# HeaderA.net
KiCad netlist of a schematic drawn in Altium Designer
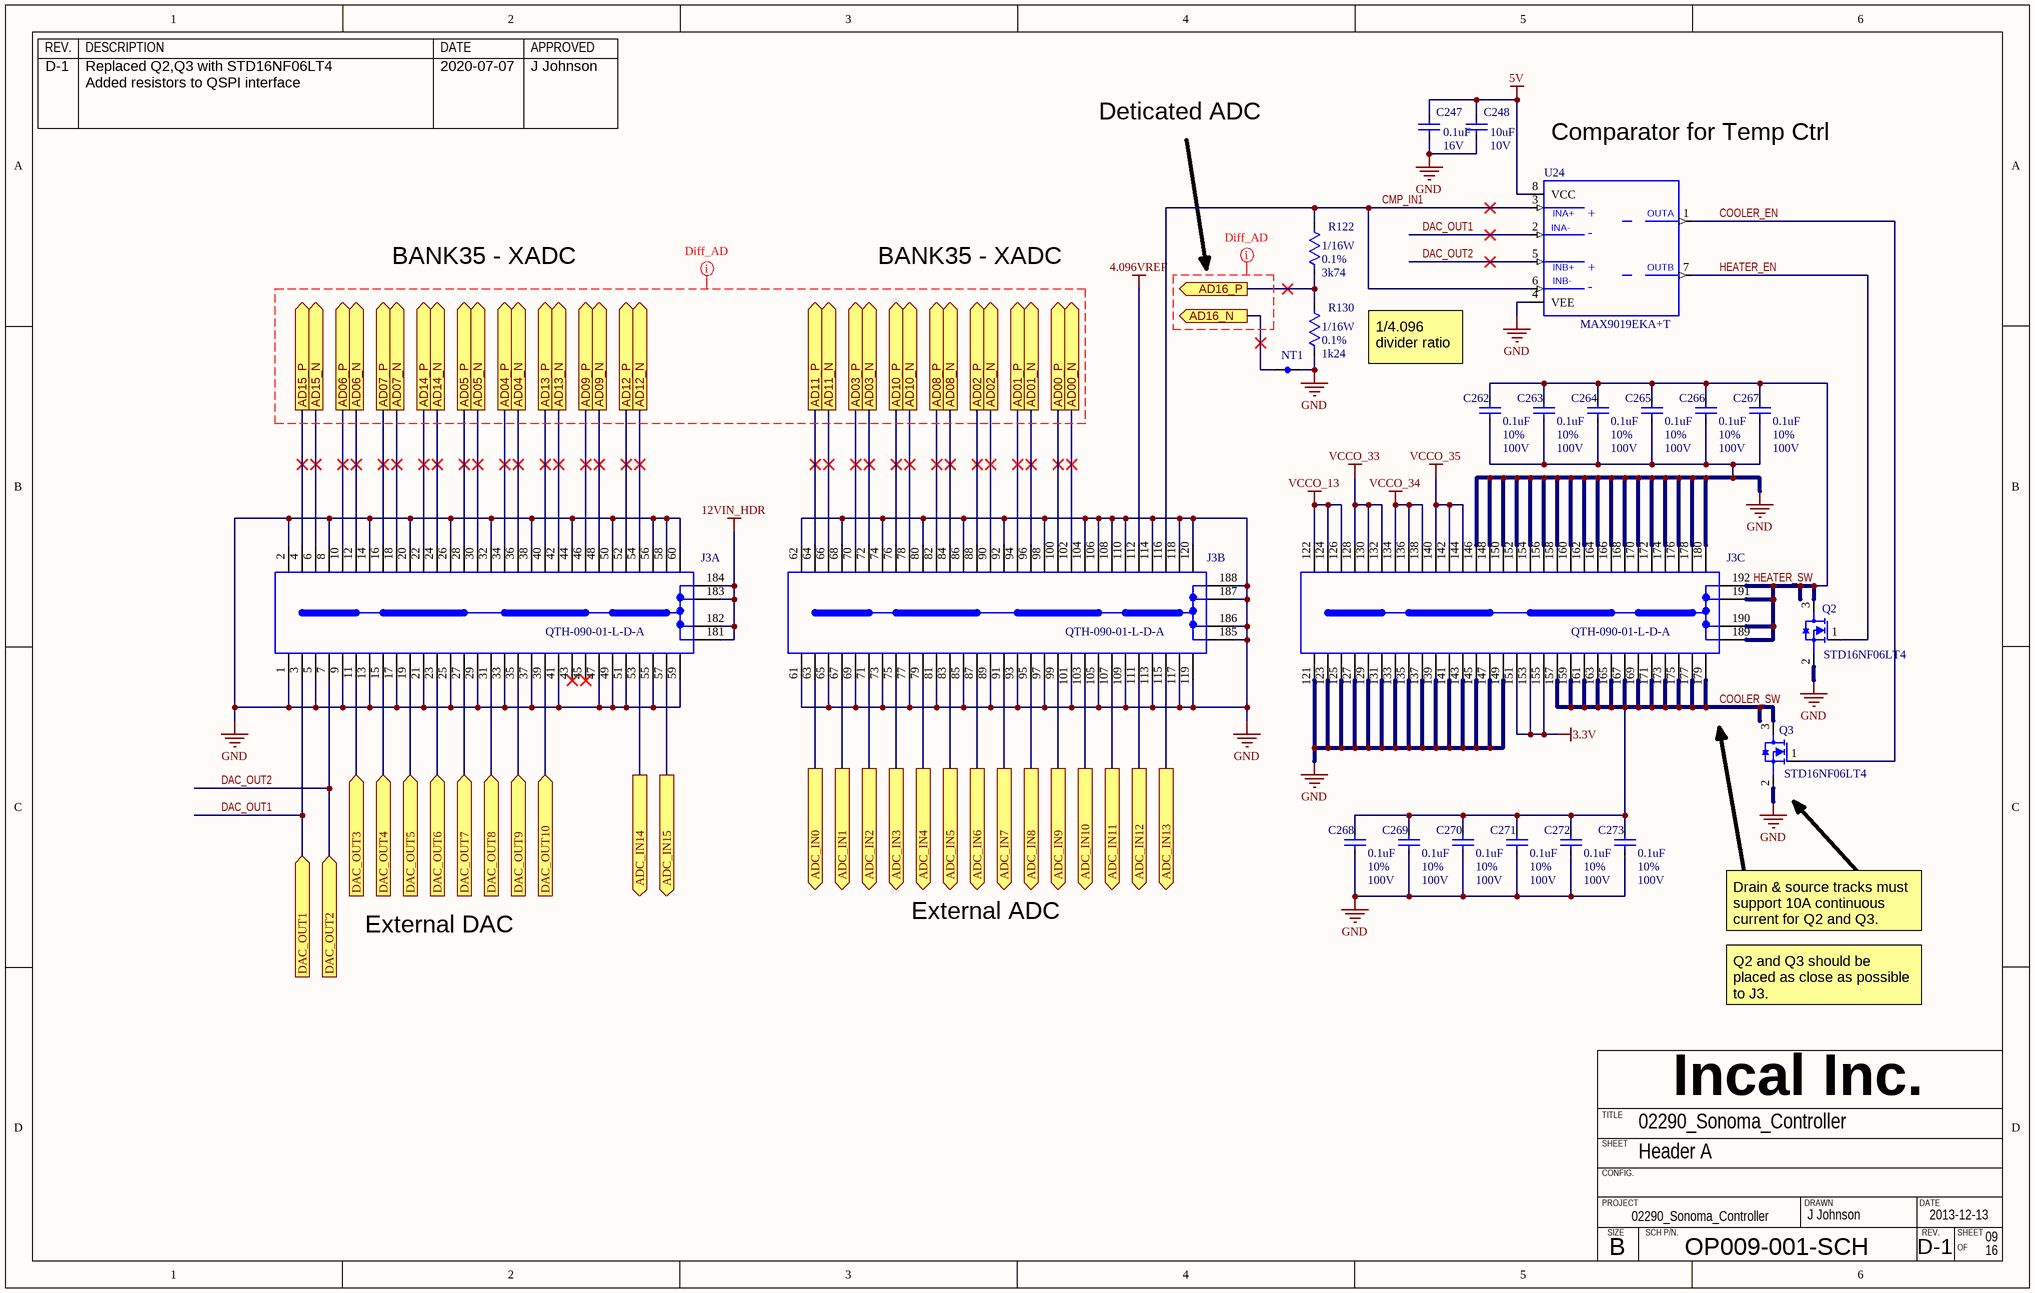
[diagram p0: HeaderA.SchDoc]

(export (version "E")
  (design (tool "Eeschema 10.0.6"))
  (components
    (comp (ref "C247")
      (value "0.1uF")
      (footprint "CAPC1005X33N")
      (description "Capacitor ceramic, X7R, 0.1uF, 16V, 10%, -55 to +125 C, EIA0402")
      (fields
        (field (name "TOLERANCE") "10%")
        (field (name "VOLTAGE") "16V")
        (field (name "Comment") "CAPACITOR_NP_TYPE1")
      )
      (libsource (lib "parts") (part "CAPACITOR_NP_TYPE1"))
    )
    (comp (ref "C248")
      (value "10uF")
      (footprint "CAPC1608X38N")
      (description "Capacitor ceramic, X5R, 10uF, 10V, 10%, -55 to +85 C, EIA0603")
      (fields
        (field (name "TOLERANCE") "10%")
        (field (name "VOLTAGE") "10V")
        (field (name "Comment") "CAPACITOR_NP_TYPE1")
      )
      (libsource (lib "parts") (part "CAPACITOR_NP_TYPE1"))
    )
    (comp (ref "C262")
      (value "0.1uF")
      (footprint "CAPC1608X38N")
      (description "Capacitor ceramic, X7R, 0.1uF, 100V, 10%, -55 to +125 C, EIA0603")
      (fields
        (field (name "TOLERANCE") "10%")
        (field (name "VOLTAGE") "100V")
        (field (name "Comment") "CAPACITOR_NP_TYPE1")
      )
      (libsource (lib "parts") (part "CAPACITOR_NP_TYPE1"))
    )
    (comp (ref "C263")
      (value "0.1uF")
      (footprint "CAPC1608X38N")
      (description "Capacitor ceramic, X7R, 0.1uF, 100V, 10%, -55 to +125 C, EIA0603")
      (fields
        (field (name "TOLERANCE") "10%")
        (field (name "VOLTAGE") "100V")
        (field (name "Comment") "CAPACITOR_NP_TYPE1")
      )
      (libsource (lib "parts") (part "CAPACITOR_NP_TYPE1"))
    )
    (comp (ref "C264")
      (value "0.1uF")
      (footprint "CAPC1608X38N")
      (description "Capacitor ceramic, X7R, 0.1uF, 100V, 10%, -55 to +125 C, EIA0603")
      (fields
        (field (name "TOLERANCE") "10%")
        (field (name "VOLTAGE") "100V")
        (field (name "Comment") "CAPACITOR_NP_TYPE1")
      )
      (libsource (lib "parts") (part "CAPACITOR_NP_TYPE1"))
    )
    (comp (ref "C265")
      (value "0.1uF")
      (footprint "CAPC1608X38N")
      (description "Capacitor ceramic, X7R, 0.1uF, 100V, 10%, -55 to +125 C, EIA0603")
      (fields
        (field (name "TOLERANCE") "10%")
        (field (name "VOLTAGE") "100V")
        (field (name "Comment") "CAPACITOR_NP_TYPE1")
      )
      (libsource (lib "parts") (part "CAPACITOR_NP_TYPE1"))
    )
    (comp (ref "C266")
      (value "0.1uF")
      (footprint "CAPC1608X38N")
      (description "Capacitor ceramic, X7R, 0.1uF, 100V, 10%, -55 to +125 C, EIA0603")
      (fields
        (field (name "TOLERANCE") "10%")
        (field (name "VOLTAGE") "100V")
        (field (name "Comment") "CAPACITOR_NP_TYPE1")
      )
      (libsource (lib "parts") (part "CAPACITOR_NP_TYPE1"))
    )
    (comp (ref "C267")
      (value "0.1uF")
      (footprint "CAPC1608X38N")
      (description "Capacitor ceramic, X7R, 0.1uF, 100V, 10%, -55 to +125 C, EIA0603")
      (fields
        (field (name "TOLERANCE") "10%")
        (field (name "VOLTAGE") "100V")
        (field (name "Comment") "CAPACITOR_NP_TYPE1")
      )
      (libsource (lib "parts") (part "CAPACITOR_NP_TYPE1"))
    )
    (comp (ref "C268")
      (value "0.1uF")
      (footprint "CAPC1608X38N")
      (description "Capacitor ceramic, X7R, 0.1uF, 100V, 10%, -55 to +125 C, EIA0603")
      (fields
        (field (name "TOLERANCE") "10%")
        (field (name "VOLTAGE") "100V")
        (field (name "Comment") "CAPACITOR_NP_TYPE1")
      )
      (libsource (lib "parts") (part "CAPACITOR_NP_TYPE1"))
    )
    (comp (ref "C269")
      (value "0.1uF")
      (footprint "CAPC1608X38N")
      (description "Capacitor ceramic, X7R, 0.1uF, 100V, 10%, -55 to +125 C, EIA0603")
      (fields
        (field (name "TOLERANCE") "10%")
        (field (name "VOLTAGE") "100V")
        (field (name "Comment") "CAPACITOR_NP_TYPE1")
      )
      (libsource (lib "parts") (part "CAPACITOR_NP_TYPE1"))
    )
    (comp (ref "C270")
      (value "0.1uF")
      (footprint "CAPC1608X38N")
      (description "Capacitor ceramic, X7R, 0.1uF, 100V, 10%, -55 to +125 C, EIA0603")
      (fields
        (field (name "TOLERANCE") "10%")
        (field (name "VOLTAGE") "100V")
        (field (name "Comment") "CAPACITOR_NP_TYPE1")
      )
      (libsource (lib "parts") (part "CAPACITOR_NP_TYPE1"))
    )
    (comp (ref "C271")
      (value "0.1uF")
      (footprint "CAPC1608X38N")
      (description "Capacitor ceramic, X7R, 0.1uF, 100V, 10%, -55 to +125 C, EIA0603")
      (fields
        (field (name "TOLERANCE") "10%")
        (field (name "VOLTAGE") "100V")
        (field (name "Comment") "CAPACITOR_NP_TYPE1")
      )
      (libsource (lib "parts") (part "CAPACITOR_NP_TYPE1"))
    )
    (comp (ref "C272")
      (value "0.1uF")
      (footprint "CAPC1608X38N")
      (description "Capacitor ceramic, X7R, 0.1uF, 100V, 10%, -55 to +125 C, EIA0603")
      (fields
        (field (name "TOLERANCE") "10%")
        (field (name "VOLTAGE") "100V")
        (field (name "Comment") "CAPACITOR_NP_TYPE1")
      )
      (libsource (lib "parts") (part "CAPACITOR_NP_TYPE1"))
    )
    (comp (ref "C273")
      (value "0.1uF")
      (footprint "CAPC1608X38N")
      (description "Capacitor ceramic, X7R, 0.1uF, 100V, 10%, -55 to +125 C, EIA0603")
      (fields
        (field (name "TOLERANCE") "10%")
        (field (name "VOLTAGE") "100V")
        (field (name "Comment") "CAPACITOR_NP_TYPE1")
      )
      (libsource (lib "parts") (part "CAPACITOR_NP_TYPE1"))
    )
    (comp (ref "J3")
      (value "QTH-090-01-L-D-A")
      (footprint "QTH-090-01-L-D-A")
      (description "Connector Header HS .5mm 180 pin DL AU")
      (libsource (lib "parts") (part "QTH-090-01-L-D-A"))
    )
    (comp (ref "NT1")
      (value "NET_TIE_1X1")
      (footprint "NET_TIE_1X1")
      (description "Net Tie 1 to 1")
      (libsource (lib "parts") (part "NET_TIE_1X1"))
    )
    (comp (ref "Q2")
      (value "STD16NF06LT4")
      (footprint "TO228P1041X238-3N")
      (description "Transistor MOSFET, N-Channel, TO-252, 60V, 24A, 40W, TO-263")
      (fields (field (name "POWER") "40W") (field (name "VOLTAGE") "60V"))
      (libsource (lib "parts") (part "TRANS_MOSFET_N-CH_TYPE2"))
    )
    (comp (ref "Q3")
      (value "STD16NF06LT4")
      (footprint "TO228P1041X238-3N")
      (description "Transistor MOSFET, N-Channel, TO-252, 60V, 24A, 40W, TO-263")
      (fields (field (name "POWER") "40W") (field (name "VOLTAGE") "60V"))
      (libsource (lib "parts") (part "TRANS_MOSFET_N-CH_TYPE2"))
    )
    (comp (ref "R122")
      (value "3k74")
      (footprint "RESC1005X33N")
      (description "Resistor, 3k74, 1/16W, 0.1%, -50 to +155 C, EIA0402, EIA(M)1005")
      (fields (field (name "VOLTAGE") "50V") (field (name "POWER") "1/16W") (field (name "TOLERANCE") "0.1%"))
      (libsource (lib "parts") (part "RESISTOR_TYPE1"))
    )
    (comp (ref "R130")
      (value "1k24")
      (footprint "RESC1005X33N")
      (description "Resistor, 1k24, 1/16W, 0.1%, -50 to +155 C, EIA0402, EIA(M)1005")
      (fields (field (name "VOLTAGE") "50V") (field (name "POWER") "1/16W") (field (name "TOLERANCE") "0.1%"))
      (libsource (lib "parts") (part "RESISTOR_TYPE1"))
    )
    (comp (ref "U24")
      (value "MAX9019EKA+T")
      (footprint "SOT65P280X145-8AN")
      (description "Comparator, Dual, Push-pull, 1.8V to 5.5V, 50mA, -40 to +85 C, , SOT-23-8")
      (fields (field (name "POWER") "Pow") (field (name "VOLTAGE") "1.8V to 5.5V"))
      (libsource (lib "parts") (part "MAX9019"))
    )
  )
  (nets
    (net (code "1") (name "/AD00_N") (class "Default")
      (node (ref "J3") (pin "102") (pinfunction "102_102") (pintype "passive"))
    )
    (net (code "2") (name "/AD00_P") (class "Default")
      (node (ref "J3") (pin "100") (pinfunction "100_100") (pintype "passive"))
    )
    (net (code "3") (name "/AD01_N") (class "Default")
      (node (ref "J3") (pin "96") (pinfunction "96_96") (pintype "passive"))
    )
    (net (code "4") (name "/AD01_P") (class "Default")
      (node (ref "J3") (pin "94") (pinfunction "94_94") (pintype "passive"))
    )
    (net (code "5") (name "/AD02_N") (class "Default")
      (node (ref "J3") (pin "90") (pinfunction "90_90") (pintype "passive"))
    )
    (net (code "6") (name "/AD02_P") (class "Default")
      (node (ref "J3") (pin "88") (pinfunction "88_88") (pintype "passive"))
    )
    (net (code "7") (name "/AD03_N") (class "Default")
      (node (ref "J3") (pin "72") (pinfunction "72_72") (pintype "passive"))
    )
    (net (code "8") (name "/AD03_P") (class "Default")
      (node (ref "J3") (pin "70") (pinfunction "70_70") (pintype "passive"))
    )
    (net (code "9") (name "/AD04_N") (class "Default")
      (node (ref "J3") (pin "36") (pinfunction "36_36") (pintype "passive"))
    )
    (net (code "10") (name "/AD04_P") (class "Default")
      (node (ref "J3") (pin "34") (pinfunction "34_34") (pintype "passive"))
    )
    (net (code "11") (name "/AD05_N") (class "Default")
      (node (ref "J3") (pin "30") (pinfunction "30_30") (pintype "passive"))
    )
    (net (code "12") (name "/AD05_P") (class "Default")
      (node (ref "J3") (pin "28") (pinfunction "28_28") (pintype "passive"))
    )
    (net (code "13") (name "/AD06_N") (class "Default")
      (node (ref "J3") (pin "12") (pinfunction "12_12") (pintype "passive"))
    )
    (net (code "14") (name "/AD06_P") (class "Default")
      (node (ref "J3") (pin "10") (pinfunction "10_10") (pintype "passive"))
    )
    (net (code "15") (name "/AD07_N") (class "Default")
      (node (ref "J3") (pin "18") (pinfunction "18_18") (pintype "passive"))
    )
    (net (code "16") (name "/AD07_P") (class "Default")
      (node (ref "J3") (pin "16") (pinfunction "16_16") (pintype "passive"))
    )
    (net (code "17") (name "/AD08_N") (class "Default")
      (node (ref "J3") (pin "84") (pinfunction "84_84") (pintype "passive"))
    )
    (net (code "18") (name "/AD08_P") (class "Default")
      (node (ref "J3") (pin "82") (pinfunction "82_82") (pintype "passive"))
    )
    (net (code "19") (name "/AD09_N") (class "Default")
      (node (ref "J3") (pin "48") (pinfunction "48_48") (pintype "passive"))
    )
    (net (code "20") (name "/AD09_P") (class "Default")
      (node (ref "J3") (pin "46") (pinfunction "46_46") (pintype "passive"))
    )
    (net (code "21") (name "/AD10_N") (class "Default")
      (node (ref "J3") (pin "78") (pinfunction "78_78") (pintype "passive"))
    )
    (net (code "22") (name "/AD10_P") (class "Default")
      (node (ref "J3") (pin "76") (pinfunction "76_76") (pintype "passive"))
    )
    (net (code "23") (name "/AD11_N") (class "Default")
      (node (ref "J3") (pin "66") (pinfunction "66_66") (pintype "passive"))
    )
    (net (code "24") (name "/AD11_P") (class "Default")
      (node (ref "J3") (pin "64") (pinfunction "64_64") (pintype "passive"))
    )
    (net (code "25") (name "/AD12_N") (class "Default")
      (node (ref "J3") (pin "54") (pinfunction "54_54") (pintype "passive"))
    )
    (net (code "26") (name "/AD12_P") (class "Default")
      (node (ref "J3") (pin "52") (pinfunction "52_52") (pintype "passive"))
    )
    (net (code "27") (name "/AD13_N") (class "Default")
      (node (ref "J3") (pin "42") (pinfunction "42_42") (pintype "passive"))
    )
    (net (code "28") (name "/AD13_P") (class "Default")
      (node (ref "J3") (pin "40") (pinfunction "40_40") (pintype "passive"))
    )
    (net (code "29") (name "/AD14_N") (class "Default")
      (node (ref "J3") (pin "24") (pinfunction "24_24") (pintype "passive"))
    )
    (net (code "30") (name "/AD14_P") (class "Default")
      (node (ref "J3") (pin "22") (pinfunction "22_22") (pintype "passive"))
    )
    (net (code "31") (name "/AD15_N") (class "Default")
      (node (ref "J3") (pin "6") (pinfunction "6_6") (pintype "passive"))
    )
    (net (code "32") (name "/AD15_P") (class "Default")
      (node (ref "J3") (pin "4") (pinfunction "4_4") (pintype "passive"))
    )
    (net (code "33") (name "/AD16_N") (class "Default")
      (node (ref "NT1") (pin "1") (pinfunction "1_1") (pintype "passive"))
    )
    (net (code "34") (name "/AD16_P") (class "Default")
      (node (ref "R122") (pin "2") (pinfunction "2_2") (pintype "passive"))
      (node (ref "R130") (pin "1") (pinfunction "1_1") (pintype "passive"))
    )
    (net (code "35") (name "/ADC_IN0") (class "Default")
      (node (ref "J3") (pin "63") (pinfunction "63_63") (pintype "passive"))
    )
    (net (code "36") (name "/ADC_IN1") (class "Default")
      (node (ref "J3") (pin "67") (pinfunction "67_67") (pintype "passive"))
    )
    (net (code "37") (name "/ADC_IN2") (class "Default")
      (node (ref "J3") (pin "71") (pinfunction "71_71") (pintype "passive"))
    )
    (net (code "38") (name "/ADC_IN3") (class "Default")
      (node (ref "J3") (pin "75") (pinfunction "75_75") (pintype "passive"))
    )
    (net (code "39") (name "/ADC_IN4") (class "Default")
      (node (ref "J3") (pin "79") (pinfunction "79_79") (pintype "passive"))
    )
    (net (code "40") (name "/ADC_IN5") (class "Default")
      (node (ref "J3") (pin "83") (pinfunction "83_83") (pintype "passive"))
    )
    (net (code "41") (name "/ADC_IN6") (class "Default")
      (node (ref "J3") (pin "87") (pinfunction "87_87") (pintype "passive"))
    )
    (net (code "42") (name "/ADC_IN7") (class "Default")
      (node (ref "J3") (pin "91") (pinfunction "91_91") (pintype "passive"))
    )
    (net (code "43") (name "/ADC_IN8") (class "Default")
      (node (ref "J3") (pin "95") (pinfunction "95_95") (pintype "passive"))
    )
    (net (code "44") (name "/ADC_IN9") (class "Default")
      (node (ref "J3") (pin "99") (pinfunction "99_99") (pintype "passive"))
    )
    (net (code "45") (name "/ADC_IN10") (class "Default")
      (node (ref "J3") (pin "103") (pinfunction "103_103") (pintype "passive"))
    )
    (net (code "46") (name "/ADC_IN11") (class "Default")
      (node (ref "J3") (pin "107") (pinfunction "107_107") (pintype "passive"))
    )
    (net (code "47") (name "/ADC_IN12") (class "Default")
      (node (ref "J3") (pin "111") (pinfunction "111_111") (pintype "passive"))
    )
    (net (code "48") (name "/ADC_IN13") (class "Default")
      (node (ref "J3") (pin "115") (pinfunction "115_115") (pintype "passive"))
    )
    (net (code "49") (name "/ADC_IN14") (class "Default")
      (node (ref "J3") (pin "53") (pinfunction "53_53") (pintype "passive"))
    )
    (net (code "50") (name "/ADC_IN15") (class "Default")
      (node (ref "J3") (pin "57") (pinfunction "57_57") (pintype "passive"))
    )
    (net (code "51") (name "/CMP_IN1") (class "Default")
      (node (ref "J3") (pin "116") (pinfunction "116_116") (pintype "passive"))
      (node (ref "R122") (pin "1") (pinfunction "1_1") (pintype "passive"))
      (node (ref "U24") (pin "3") (pinfunction "INA+_3") (pintype "input"))
      (node (ref "U24") (pin "6") (pinfunction "INB-_6") (pintype "input"))
    )
    (net (code "52") (name "/COOLER_EN") (class "Default")
      (node (ref "Q3") (pin "1") (pinfunction "G_1") (pintype "passive"))
      (node (ref "U24") (pin "1") (pinfunction "OUTA_1") (pintype "output"))
    )
    (net (code "53") (name "/COOLER_SW") (class "Default")
      (node (ref "C268") (pin "1") (pinfunction "1_1") (pintype "passive"))
      (node (ref "C269") (pin "1") (pinfunction "1_1") (pintype "passive"))
      (node (ref "C270") (pin "1") (pinfunction "1_1") (pintype "passive"))
      (node (ref "C271") (pin "1") (pinfunction "1_1") (pintype "passive"))
      (node (ref "C272") (pin "1") (pinfunction "1_1") (pintype "passive"))
      (node (ref "C273") (pin "1") (pinfunction "1_1") (pintype "passive"))
      (node (ref "J3") (pin "157") (pinfunction "157_157") (pintype "passive"))
      (node (ref "J3") (pin "159") (pinfunction "159_159") (pintype "passive"))
      (node (ref "J3") (pin "161") (pinfunction "161_161") (pintype "passive"))
      (node (ref "J3") (pin "163") (pinfunction "163_163") (pintype "passive"))
      (node (ref "J3") (pin "165") (pinfunction "165_165") (pintype "passive"))
      (node (ref "J3") (pin "167") (pinfunction "167_167") (pintype "passive"))
      (node (ref "J3") (pin "169") (pinfunction "169_169") (pintype "passive"))
      (node (ref "J3") (pin "171") (pinfunction "171_171") (pintype "passive"))
      (node (ref "J3") (pin "173") (pinfunction "173_173") (pintype "passive"))
      (node (ref "J3") (pin "175") (pinfunction "175_175") (pintype "passive"))
      (node (ref "J3") (pin "177") (pinfunction "177_177") (pintype "passive"))
      (node (ref "J3") (pin "179") (pinfunction "179_179") (pintype "passive"))
      (node (ref "Q3") (pin "3") (pinfunction "D_3") (pintype "passive"))
    )
    (net (code "54") (name "/DAC_OUT1") (class "Default")
      (node (ref "J3") (pin "3") (pinfunction "3_3") (pintype "passive"))
      (node (ref "U24") (pin "2") (pinfunction "INA-_2") (pintype "input"))
    )
    (net (code "55") (name "/DAC_OUT2") (class "Default")
      (node (ref "J3") (pin "7") (pinfunction "7_7") (pintype "passive"))
      (node (ref "U24") (pin "5") (pinfunction "INB+_5") (pintype "input"))
    )
    (net (code "56") (name "/DAC_OUT3") (class "Default")
      (node (ref "J3") (pin "11") (pinfunction "11_11") (pintype "passive"))
    )
    (net (code "57") (name "/DAC_OUT4") (class "Default")
      (node (ref "J3") (pin "15") (pinfunction "15_15") (pintype "passive"))
    )
    (net (code "58") (name "/DAC_OUT5") (class "Default")
      (node (ref "J3") (pin "19") (pinfunction "19_19") (pintype "passive"))
    )
    (net (code "59") (name "/DAC_OUT6") (class "Default")
      (node (ref "J3") (pin "23") (pinfunction "23_23") (pintype "passive"))
    )
    (net (code "60") (name "/DAC_OUT7") (class "Default")
      (node (ref "J3") (pin "27") (pinfunction "27_27") (pintype "passive"))
    )
    (net (code "61") (name "/DAC_OUT8") (class "Default")
      (node (ref "J3") (pin "31") (pinfunction "31_31") (pintype "passive"))
    )
    (net (code "62") (name "/DAC_OUT9") (class "Default")
      (node (ref "J3") (pin "35") (pinfunction "35_35") (pintype "passive"))
    )
    (net (code "63") (name "/DAC_OUT10") (class "Default")
      (node (ref "J3") (pin "39") (pinfunction "39_39") (pintype "passive"))
    )
    (net (code "64") (name "/HEATER_EN") (class "Default")
      (node (ref "Q2") (pin "1") (pinfunction "G_1") (pintype "passive"))
      (node (ref "U24") (pin "7") (pinfunction "OUTB_7") (pintype "output"))
    )
    (net (code "65") (name "/HEATER_SW") (class "Default")
      (node (ref "C262") (pin "1") (pinfunction "1_1") (pintype "passive"))
      (node (ref "C263") (pin "1") (pinfunction "1_1") (pintype "passive"))
      (node (ref "C264") (pin "1") (pinfunction "1_1") (pintype "passive"))
      (node (ref "C265") (pin "1") (pinfunction "1_1") (pintype "passive"))
      (node (ref "C266") (pin "1") (pinfunction "1_1") (pintype "passive"))
      (node (ref "C267") (pin "1") (pinfunction "1_1") (pintype "passive"))
      (node (ref "J3") (pin "189") (pinfunction "189_189") (pintype "passive"))
      (node (ref "J3") (pin "190") (pinfunction "190_190") (pintype "passive"))
      (node (ref "J3") (pin "191") (pinfunction "191_191") (pintype "passive"))
      (node (ref "J3") (pin "192") (pinfunction "192_192") (pintype "passive"))
      (node (ref "Q2") (pin "3") (pinfunction "D_3") (pintype "passive"))
    )
    (net (code "66") (name "3.3V") (class "Default")
      (node (ref "J3") (pin "151") (pinfunction "151_151") (pintype "passive"))
      (node (ref "J3") (pin "153") (pinfunction "153_153") (pintype "passive"))
      (node (ref "J3") (pin "155") (pinfunction "155_155") (pintype "passive"))
    )
    (net (code "67") (name "4.096VREF") (class "Default")
      (node (ref "J3") (pin "112") (pinfunction "112_112") (pintype "passive"))
    )
    (net (code "68") (name "5V") (class "Default")
      (node (ref "C247") (pin "1") (pinfunction "1_1") (pintype "passive"))
      (node (ref "C248") (pin "1") (pinfunction "1_1") (pintype "passive"))
      (node (ref "U24") (pin "8") (pinfunction "VCC_8") (pintype "power_in"))
    )
    (net (code "69") (name "12VIN_HDR") (class "Default")
      (node (ref "J3") (pin "181") (pinfunction "181_181") (pintype "passive"))
      (node (ref "J3") (pin "182") (pinfunction "182_182") (pintype "passive"))
      (node (ref "J3") (pin "183") (pinfunction "183_183") (pintype "passive"))
      (node (ref "J3") (pin "184") (pinfunction "184_184") (pintype "passive"))
    )
    (net (code "70") (name "GND") (class "Default")
      (node (ref "C247") (pin "2") (pinfunction "2_2") (pintype "passive"))
      (node (ref "C248") (pin "2") (pinfunction "2_2") (pintype "passive"))
      (node (ref "C262") (pin "2") (pinfunction "2_2") (pintype "passive"))
      (node (ref "C263") (pin "2") (pinfunction "2_2") (pintype "passive"))
      (node (ref "C264") (pin "2") (pinfunction "2_2") (pintype "passive"))
      (node (ref "C265") (pin "2") (pinfunction "2_2") (pintype "passive"))
      (node (ref "C266") (pin "2") (pinfunction "2_2") (pintype "passive"))
      (node (ref "C267") (pin "2") (pinfunction "2_2") (pintype "passive"))
      (node (ref "C268") (pin "2") (pinfunction "2_2") (pintype "passive"))
      (node (ref "C269") (pin "2") (pinfunction "2_2") (pintype "passive"))
      (node (ref "C270") (pin "2") (pinfunction "2_2") (pintype "passive"))
      (node (ref "C271") (pin "2") (pinfunction "2_2") (pintype "passive"))
      (node (ref "C272") (pin "2") (pinfunction "2_2") (pintype "passive"))
      (node (ref "C273") (pin "2") (pinfunction "2_2") (pintype "passive"))
      (node (ref "J3") (pin "1") (pinfunction "1_1") (pintype "passive"))
      (node (ref "J3") (pin "101") (pinfunction "101_101") (pintype "passive"))
      (node (ref "J3") (pin "104") (pinfunction "104_104") (pintype "passive"))
      (node (ref "J3") (pin "105") (pinfunction "105_105") (pintype "passive"))
      (node (ref "J3") (pin "106") (pinfunction "106_106") (pintype "passive"))
      (node (ref "J3") (pin "108") (pinfunction "108_108") (pintype "passive"))
      (node (ref "J3") (pin "109") (pinfunction "109_109") (pintype "passive"))
      (node (ref "J3") (pin "110") (pinfunction "110_110") (pintype "passive"))
      (node (ref "J3") (pin "113") (pinfunction "113_113") (pintype "passive"))
      (node (ref "J3") (pin "114") (pinfunction "114_114") (pintype "passive"))
      (node (ref "J3") (pin "117") (pinfunction "117_117") (pintype "passive"))
      (node (ref "J3") (pin "118") (pinfunction "118_118") (pintype "passive"))
      (node (ref "J3") (pin "119") (pinfunction "119_119") (pintype "passive"))
      (node (ref "J3") (pin "120") (pinfunction "120_120") (pintype "passive"))
      (node (ref "J3") (pin "121") (pinfunction "121_121") (pintype "passive"))
      (node (ref "J3") (pin "123") (pinfunction "123_123") (pintype "passive"))
      (node (ref "J3") (pin "125") (pinfunction "125_125") (pintype "passive"))
      (node (ref "J3") (pin "127") (pinfunction "127_127") (pintype "passive"))
      (node (ref "J3") (pin "129") (pinfunction "129_129") (pintype "passive"))
      (node (ref "J3") (pin "13") (pinfunction "13_13") (pintype "passive"))
      (node (ref "J3") (pin "131") (pinfunction "131_131") (pintype "passive"))
      (node (ref "J3") (pin "133") (pinfunction "133_133") (pintype "passive"))
      (node (ref "J3") (pin "135") (pinfunction "135_135") (pintype "passive"))
      (node (ref "J3") (pin "137") (pinfunction "137_137") (pintype "passive"))
      (node (ref "J3") (pin "139") (pinfunction "139_139") (pintype "passive"))
      (node (ref "J3") (pin "14") (pinfunction "14_14") (pintype "passive"))
      (node (ref "J3") (pin "141") (pinfunction "141_141") (pintype "passive"))
      (node (ref "J3") (pin "143") (pinfunction "143_143") (pintype "passive"))
      (node (ref "J3") (pin "145") (pinfunction "145_145") (pintype "passive"))
      (node (ref "J3") (pin "146") (pinfunction "146_146") (pintype "passive"))
      (node (ref "J3") (pin "147") (pinfunction "147_147") (pintype "passive"))
      (node (ref "J3") (pin "148") (pinfunction "148_148") (pintype "passive"))
      (node (ref "J3") (pin "149") (pinfunction "149_149") (pintype "passive"))
      (node (ref "J3") (pin "150") (pinfunction "150_150") (pintype "passive"))
      (node (ref "J3") (pin "152") (pinfunction "152_152") (pintype "passive"))
      (node (ref "J3") (pin "154") (pinfunction "154_154") (pintype "passive"))
      (node (ref "J3") (pin "156") (pinfunction "156_156") (pintype "passive"))
      (node (ref "J3") (pin "158") (pinfunction "158_158") (pintype "passive"))
      (node (ref "J3") (pin "160") (pinfunction "160_160") (pintype "passive"))
      (node (ref "J3") (pin "162") (pinfunction "162_162") (pintype "passive"))
      (node (ref "J3") (pin "164") (pinfunction "164_164") (pintype "passive"))
      (node (ref "J3") (pin "166") (pinfunction "166_166") (pintype "passive"))
      (node (ref "J3") (pin "168") (pinfunction "168_168") (pintype "passive"))
      (node (ref "J3") (pin "17") (pinfunction "17_17") (pintype "passive"))
      (node (ref "J3") (pin "170") (pinfunction "170_170") (pintype "passive"))
      (node (ref "J3") (pin "172") (pinfunction "172_172") (pintype "passive"))
      (node (ref "J3") (pin "174") (pinfunction "174_174") (pintype "passive"))
      (node (ref "J3") (pin "176") (pinfunction "176_176") (pintype "passive"))
      (node (ref "J3") (pin "178") (pinfunction "178_178") (pintype "passive"))
      (node (ref "J3") (pin "180") (pinfunction "180_180") (pintype "passive"))
      (node (ref "J3") (pin "185") (pinfunction "185_185") (pintype "passive"))
      (node (ref "J3") (pin "186") (pinfunction "186_186") (pintype "passive"))
      (node (ref "J3") (pin "187") (pinfunction "187_187") (pintype "passive"))
      (node (ref "J3") (pin "188") (pinfunction "188_188") (pintype "passive"))
      (node (ref "J3") (pin "2") (pinfunction "2_2") (pintype "passive"))
      (node (ref "J3") (pin "20") (pinfunction "20_20") (pintype "passive"))
      (node (ref "J3") (pin "21") (pinfunction "21_21") (pintype "passive"))
      (node (ref "J3") (pin "25") (pinfunction "25_25") (pintype "passive"))
      (node (ref "J3") (pin "26") (pinfunction "26_26") (pintype "passive"))
      (node (ref "J3") (pin "29") (pinfunction "29_29") (pintype "passive"))
      (node (ref "J3") (pin "32") (pinfunction "32_32") (pintype "passive"))
      (node (ref "J3") (pin "33") (pinfunction "33_33") (pintype "passive"))
      (node (ref "J3") (pin "37") (pinfunction "37_37") (pintype "passive"))
      (node (ref "J3") (pin "38") (pinfunction "38_38") (pintype "passive"))
      (node (ref "J3") (pin "41") (pinfunction "41_41") (pintype "passive"))
      (node (ref "J3") (pin "44") (pinfunction "44_44") (pintype "passive"))
      (node (ref "J3") (pin "47") (pinfunction "47_47") (pintype "passive"))
      (node (ref "J3") (pin "49") (pinfunction "49_49") (pintype "passive"))
      (node (ref "J3") (pin "5") (pinfunction "5_5") (pintype "passive"))
      (node (ref "J3") (pin "50") (pinfunction "50_50") (pintype "passive"))
      (node (ref "J3") (pin "51") (pinfunction "51_51") (pintype "passive"))
      (node (ref "J3") (pin "55") (pinfunction "55_55") (pintype "passive"))
      (node (ref "J3") (pin "56") (pinfunction "56_56") (pintype "passive"))
      (node (ref "J3") (pin "58") (pinfunction "58_58") (pintype "passive"))
      (node (ref "J3") (pin "59") (pinfunction "59_59") (pintype "passive"))
      (node (ref "J3") (pin "60") (pinfunction "60_60") (pintype "passive"))
      (node (ref "J3") (pin "61") (pinfunction "61_61") (pintype "passive"))
      (node (ref "J3") (pin "62") (pinfunction "62_62") (pintype "passive"))
      (node (ref "J3") (pin "65") (pinfunction "65_65") (pintype "passive"))
      (node (ref "J3") (pin "68") (pinfunction "68_68") (pintype "passive"))
      (node (ref "J3") (pin "69") (pinfunction "69_69") (pintype "passive"))
      (node (ref "J3") (pin "73") (pinfunction "73_73") (pintype "passive"))
      (node (ref "J3") (pin "74") (pinfunction "74_74") (pintype "passive"))
      (node (ref "J3") (pin "77") (pinfunction "77_77") (pintype "passive"))
      (node (ref "J3") (pin "8") (pinfunction "8_8") (pintype "passive"))
      (node (ref "J3") (pin "80") (pinfunction "80_80") (pintype "passive"))
      (node (ref "J3") (pin "81") (pinfunction "81_81") (pintype "passive"))
      (node (ref "J3") (pin "85") (pinfunction "85_85") (pintype "passive"))
      (node (ref "J3") (pin "86") (pinfunction "86_86") (pintype "passive"))
      (node (ref "J3") (pin "89") (pinfunction "89_89") (pintype "passive"))
      (node (ref "J3") (pin "9") (pinfunction "9_9") (pintype "passive"))
      (node (ref "J3") (pin "92") (pinfunction "92_92") (pintype "passive"))
      (node (ref "J3") (pin "93") (pinfunction "93_93") (pintype "passive"))
      (node (ref "J3") (pin "97") (pinfunction "97_97") (pintype "passive"))
      (node (ref "J3") (pin "98") (pinfunction "98_98") (pintype "passive"))
      (node (ref "NT1") (pin "2") (pinfunction "2_2") (pintype "passive"))
      (node (ref "Q2") (pin "2") (pinfunction "S_2") (pintype "passive"))
      (node (ref "Q3") (pin "2") (pinfunction "S_2") (pintype "passive"))
      (node (ref "R130") (pin "2") (pinfunction "2_2") (pintype "passive"))
      (node (ref "U24") (pin "4") (pinfunction "VEE_4") (pintype "power_in"))
    )
    (net (code "71") (name "VCCO_13") (class "Default")
      (node (ref "J3") (pin "122") (pinfunction "122_122") (pintype "passive"))
      (node (ref "J3") (pin "124") (pinfunction "124_124") (pintype "passive"))
      (node (ref "J3") (pin "126") (pinfunction "126_126") (pintype "passive"))
    )
    (net (code "72") (name "VCCO_33") (class "Default")
      (node (ref "J3") (pin "128") (pinfunction "128_128") (pintype "passive"))
      (node (ref "J3") (pin "130") (pinfunction "130_130") (pintype "passive"))
      (node (ref "J3") (pin "132") (pinfunction "132_132") (pintype "passive"))
    )
    (net (code "73") (name "VCCO_34") (class "Default")
      (node (ref "J3") (pin "134") (pinfunction "134_134") (pintype "passive"))
      (node (ref "J3") (pin "136") (pinfunction "136_136") (pintype "passive"))
      (node (ref "J3") (pin "138") (pinfunction "138_138") (pintype "passive"))
    )
    (net (code "74") (name "VCCO_35") (class "Default")
      (node (ref "J3") (pin "140") (pinfunction "140_140") (pintype "passive"))
      (node (ref "J3") (pin "142") (pinfunction "142_142") (pintype "passive"))
      (node (ref "J3") (pin "144") (pinfunction "144_144") (pintype "passive"))
    )
    (net (code "75") (name "unconnected-(J3-Pad43)") (class "Default")
      (node (ref "J3") (pin "43") (pinfunction "43_43") (pintype "passive+no_connect"))
    )
    (net (code "76") (name "unconnected-(J3-Pad45)") (class "Default")
      (node (ref "J3") (pin "45") (pinfunction "45_45") (pintype "passive+no_connect"))
    )
  )
)
